# Adafruit_TMP117.net
KiCad netlist of a schematic drawn in EAGLE
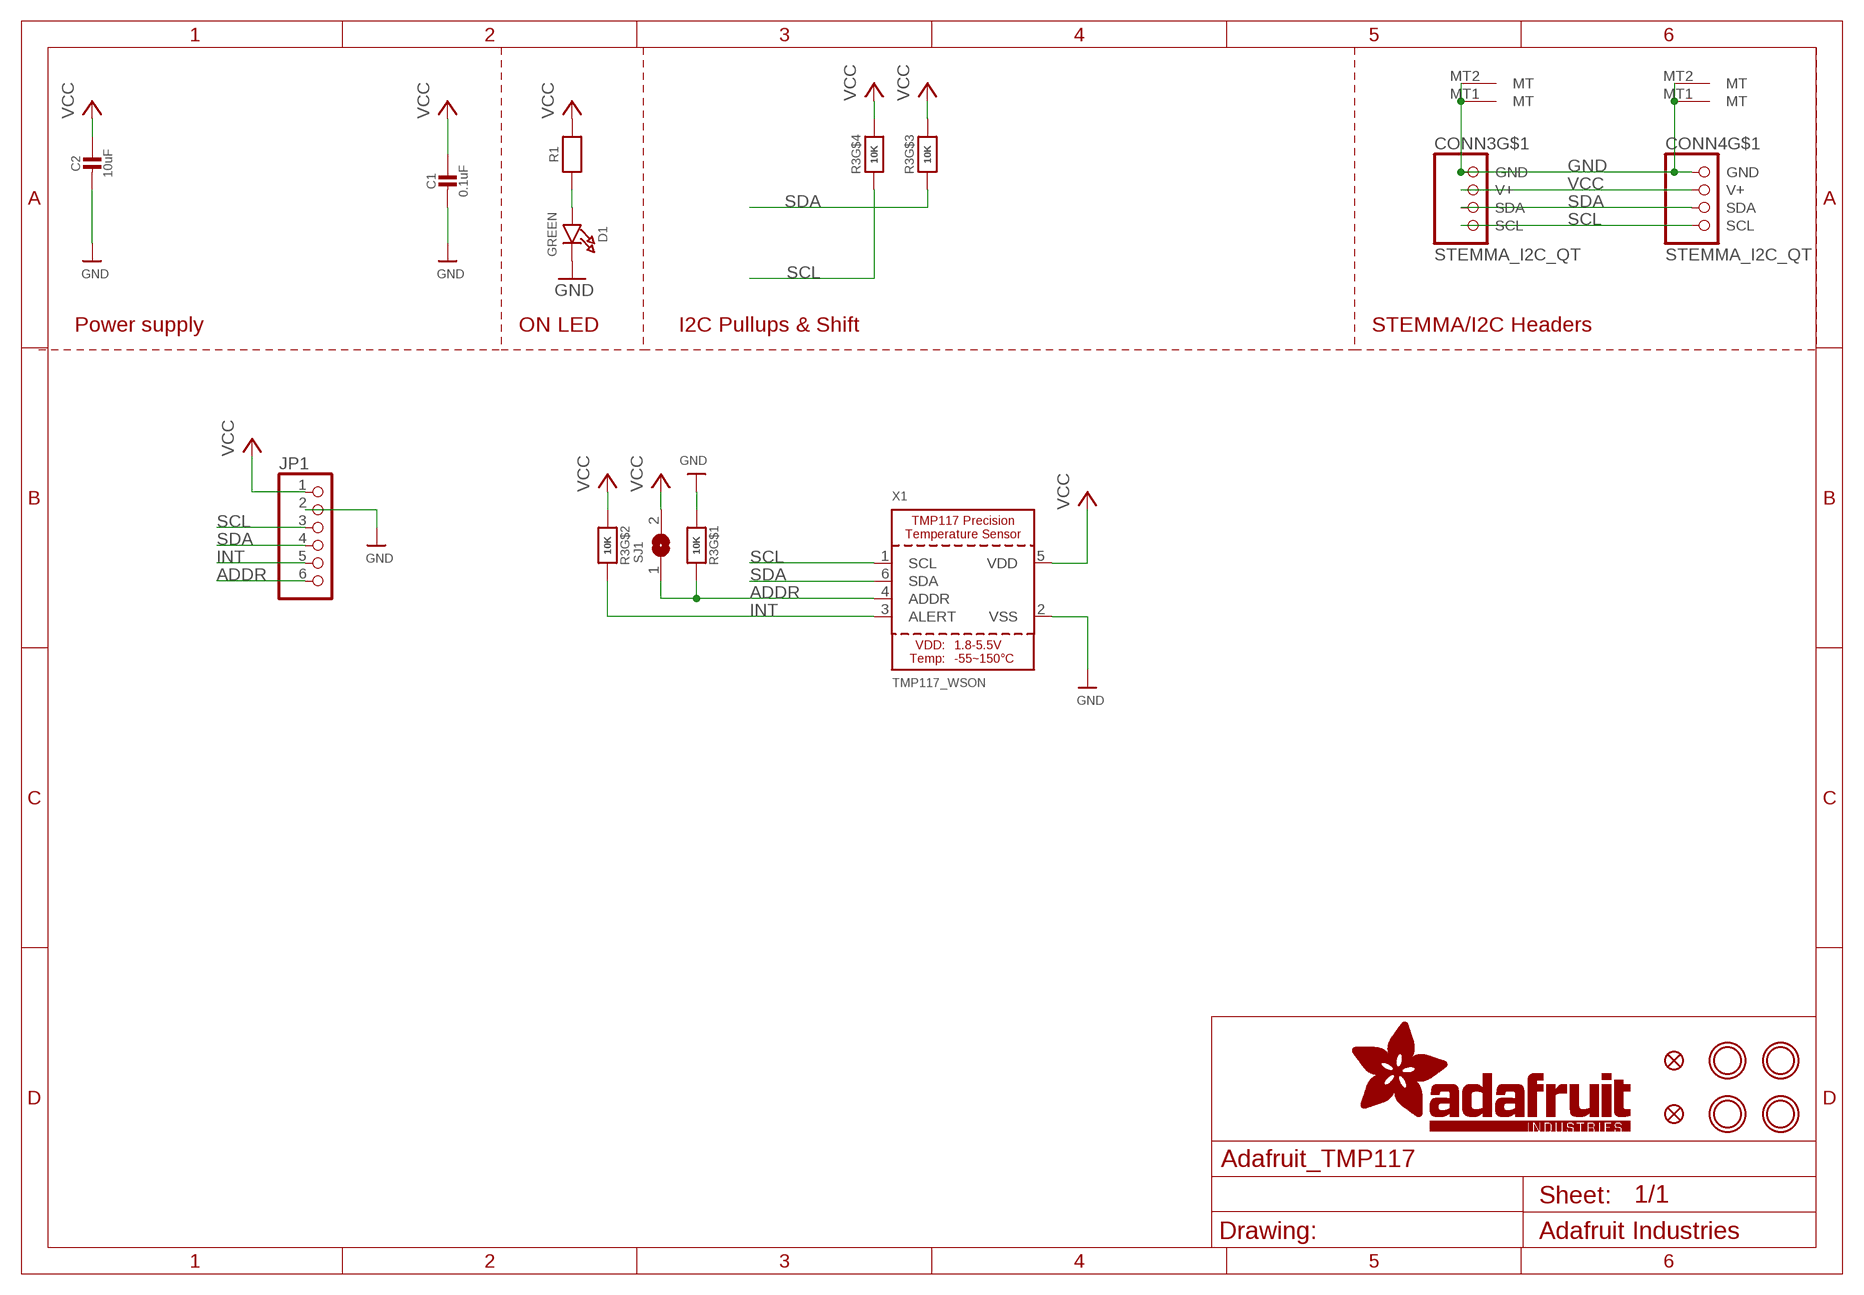
[diagram p0: schematic, sheet 1]

(export (version "E")
  (design (tool "Eeschema 10.0.6"))
  (components
    (comp (ref "C1")
      (value "0.1uF")
      (footprint "eagle-import:0603-NO")
      (libsource (lib "eagle-import") (part "CAP_CERAMIC0603_NO"))
    )
    (comp (ref "C2")
      (value "10uF")
      (footprint "eagle-import:0805-NO")
      (libsource (lib "eagle-import") (part "CAP_CERAMIC0805-NOOUTLINE"))
    )
    (comp (ref "CONN3")
      (value "STEMMA_I2C_QT")
      (footprint "eagle-import:JST_SH4")
      (libsource (lib "eagle-import") (part "STEMMA_I2C_QT"))
    )
    (comp (ref "CONN4")
      (value "STEMMA_I2C_QT")
      (footprint "eagle-import:JST_SH4")
      (libsource (lib "eagle-import") (part "STEMMA_I2C_QT"))
    )
    (comp (ref "D1")
      (value "GREEN")
      (footprint "eagle-import:CHIPLED_0603_NOOUTLINE")
      (libsource (lib "eagle-import") (part "LED0603_NOOUTLINE"))
    )
    (comp (ref "FID3")
      (value "FIDUCIAL_1MM")
      (footprint "eagle-import:FIDUCIAL_1MM")
      (libsource (lib "eagle-import") (part "FIDUCIAL_1MM"))
    )
    (comp (ref "FID4")
      (value "FIDUCIAL_1MM")
      (footprint "eagle-import:FIDUCIAL_1MM")
      (libsource (lib "eagle-import") (part "FIDUCIAL_1MM"))
    )
    (comp (ref "JP1")
      (value "HEADER-1X670MIL")
      (footprint "eagle-import:1X06_ROUND_70")
      (libsource (lib "eagle-import") (part "HEADER-1X670MIL"))
    )
    (comp (ref "R1")
      (value "RESISTOR_0603_NOOUT")
      (footprint "eagle-import:0603-NO")
      (libsource (lib "eagle-import") (part "RESISTOR_0603_NOOUT"))
    )
    (comp (ref "R3")
      (value "10K")
      (footprint "eagle-import:RESPACK_4X0603")
      (libsource (lib "eagle-import") (part "RESISTOR_4PACK"))
    )
    (comp (ref "SJ1")
      (value "SOLDERJUMPER")
      (footprint "eagle-import:SOLDERJUMPER_ARROW_NOPASTE")
      (libsource (lib "eagle-import") (part "SOLDERJUMPER"))
    )
    (comp (ref "U$1")
      (value "MOUNTINGHOLE2.5")
      (footprint "eagle-import:MOUNTINGHOLE_2.5_PLATED")
      (libsource (lib "eagle-import") (part "MOUNTINGHOLE2.5"))
    )
    (comp (ref "U$17")
      (value "MOUNTINGHOLE2.5")
      (footprint "eagle-import:MOUNTINGHOLE_2.5_PLATED")
      (libsource (lib "eagle-import") (part "MOUNTINGHOLE2.5"))
    )
    (comp (ref "U$19")
      (value "MOUNTINGHOLE2.5")
      (footprint "eagle-import:MOUNTINGHOLE_2.5_PLATED")
      (libsource (lib "eagle-import") (part "MOUNTINGHOLE2.5"))
    )
    (comp (ref "U$21")
      (value "MOUNTINGHOLE2.5")
      (footprint "eagle-import:MOUNTINGHOLE_2.5_PLATED")
      (libsource (lib "eagle-import") (part "MOUNTINGHOLE2.5"))
    )
    (comp (ref "X1")
      (value "TMP117_WSON")
      (footprint "eagle-import:WSON-6")
      (libsource (lib "eagle-import") (part "TMP117_WSON"))
    )
  )
  (nets
    (net (code "1") (name "/ADDR") (class "Default")
      (node (ref "JP1") (pin "6") (pinfunction "6_6") (pintype "passive"))
      (node (ref "R3") (pin "8") (pinfunction "2_8") (pintype "passive"))
      (node (ref "SJ1") (pin "1") (pinfunction "1_1") (pintype "passive"))
      (node (ref "X1") (pin "4") (pinfunction "ADDR_4") (pintype "input"))
    )
    (net (code "2") (name "/INT") (class "Default")
      (node (ref "JP1") (pin "5") (pinfunction "5_5") (pintype "passive"))
      (node (ref "R3") (pin "7") (pinfunction "2_7") (pintype "passive"))
      (node (ref "X1") (pin "3") (pinfunction "ALERT_3") (pintype "output"))
    )
    (net (code "3") (name "/SCL") (class "Default")
      (node (ref "CONN3") (pin "4") (pinfunction "SCL_4") (pintype "passive"))
      (node (ref "CONN4") (pin "4") (pinfunction "SCL_4") (pintype "passive"))
      (node (ref "JP1") (pin "3") (pinfunction "3_3") (pintype "passive"))
      (node (ref "R3") (pin "4") (pinfunction "1_4") (pintype "passive"))
      (node (ref "X1") (pin "1") (pinfunction "SCL_1") (pintype "bidirectional"))
    )
    (net (code "4") (name "/SDA") (class "Default")
      (node (ref "CONN3") (pin "3") (pinfunction "SDA_3") (pintype "passive"))
      (node (ref "CONN4") (pin "3") (pinfunction "SDA_3") (pintype "passive"))
      (node (ref "JP1") (pin "4") (pinfunction "4_4") (pintype "passive"))
      (node (ref "R3") (pin "3") (pinfunction "1_3") (pintype "passive"))
      (node (ref "X1") (pin "6") (pinfunction "SDA_6") (pintype "bidirectional"))
    )
    (net (code "5") (name "GND") (class "Default")
      (node (ref "C1") (pin "2") (pinfunction "2_2") (pintype "passive"))
      (node (ref "C2") (pin "2") (pinfunction "2_2") (pintype "passive"))
      (node (ref "CONN3") (pin "1") (pinfunction "GND_1") (pintype "passive"))
      (node (ref "CONN3") (pin "MT1") (pinfunction "MT_MT1") (pintype "bidirectional"))
      (node (ref "CONN3") (pin "MT2") (pinfunction "MT_MT2") (pintype "bidirectional"))
      (node (ref "CONN4") (pin "1") (pinfunction "GND_1") (pintype "passive"))
      (node (ref "CONN4") (pin "MT1") (pinfunction "MT_MT1") (pintype "bidirectional"))
      (node (ref "CONN4") (pin "MT2") (pinfunction "MT_MT2") (pintype "bidirectional"))
      (node (ref "D1") (pin "C") (pinfunction "C_C") (pintype "passive"))
      (node (ref "JP1") (pin "2") (pinfunction "2_2") (pintype "passive"))
      (node (ref "R3") (pin "1") (pinfunction "1_1") (pintype "passive"))
      (node (ref "X1") (pin "2") (pinfunction "VSS_2") (pintype "power_in"))
    )
    (net (code "6") (name "Net-(D1-PadA)") (class "Default")
      (node (ref "D1") (pin "A") (pinfunction "A_A") (pintype "passive"))
      (node (ref "R1") (pin "1") (pinfunction "1_1") (pintype "passive"))
    )
    (net (code "7") (name "VCC") (class "Default")
      (node (ref "C1") (pin "1") (pinfunction "1_1") (pintype "passive"))
      (node (ref "C2") (pin "1") (pinfunction "1_1") (pintype "passive"))
      (node (ref "CONN3") (pin "2") (pinfunction "V+_2") (pintype "passive"))
      (node (ref "CONN4") (pin "2") (pinfunction "V+_2") (pintype "passive"))
      (node (ref "JP1") (pin "1") (pinfunction "1_1") (pintype "passive"))
      (node (ref "R1") (pin "2") (pinfunction "2_2") (pintype "passive"))
      (node (ref "R3") (pin "2") (pinfunction "1_2") (pintype "passive"))
      (node (ref "R3") (pin "5") (pinfunction "2_5") (pintype "passive"))
      (node (ref "R3") (pin "6") (pinfunction "2_6") (pintype "passive"))
      (node (ref "SJ1") (pin "2") (pinfunction "2_2") (pintype "passive"))
      (node (ref "X1") (pin "5") (pinfunction "VDD_5") (pintype "power_in"))
    )
  )
)
